# Shield_Amir_EDO_V_0_0.net
KiCad netlist of a schematic drawn in EasyEDA
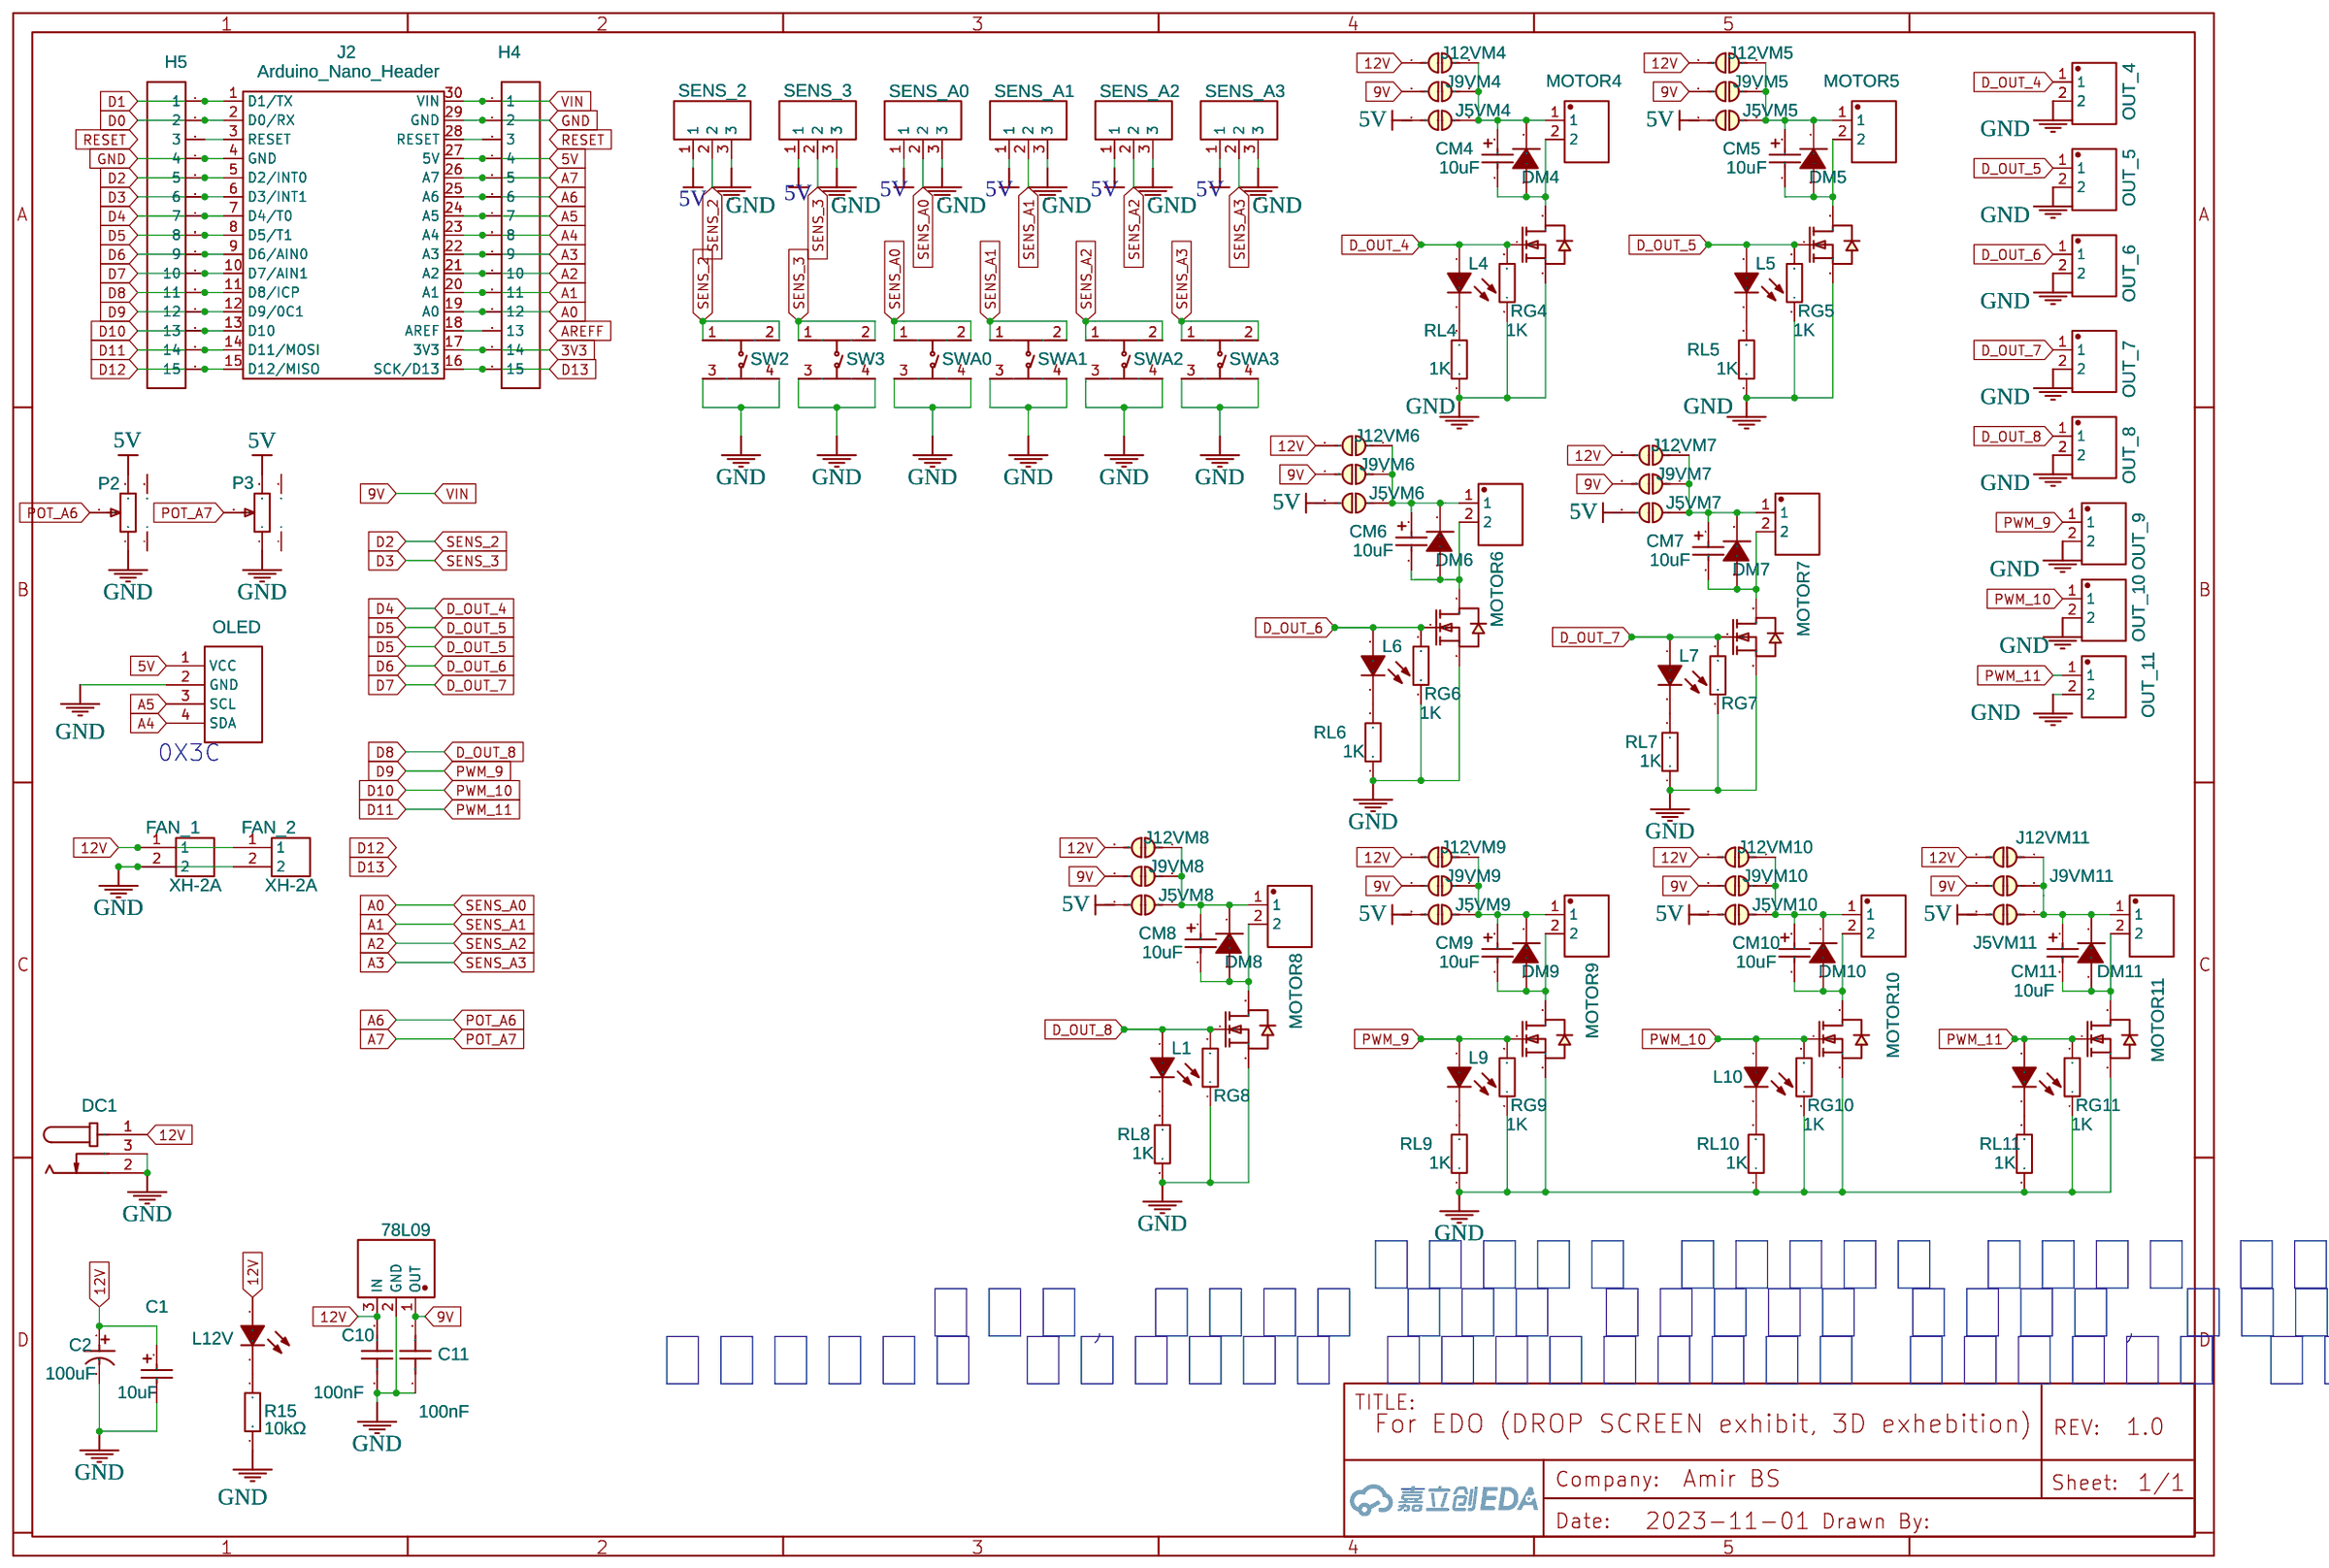
[diagram p0: schematic sheet]

(export (version "E")
  (design (tool "Eeschema 10.0.6"))
  (components
    (comp (ref "C1")
      (value "10uF")
      (fields (field (name "Manufacturer Part") "TAJA106K016RNJ") (field (name "Manufacturer") "Kyocera AVX"))
      (libsource (lib "") (part "TAJA106K016RNJ_1"))
    )
    (comp (ref "C2")
      (value "100uF")
      (fields
        (field (name "Manufacturer Part") "KM107M035E11RR0VH2FP0")
        (field (name "Manufacturer") "CX(承兴)")
      )
      (libsource (lib "") (part "100uF 35V 6.3*11"))
    )
    (comp (ref "C10")
      (value "100nF")
      (fields
        (field (name "Manufacturer Part") "CC0603KRX7R9BB104")
        (field (name "Manufacturer") "YAGEO(国巨)")
      )
      (libsource (lib "") (part "CC0603KRX7R9BB104"))
    )
    (comp (ref "C11")
      (value "100nF")
      (fields
        (field (name "Manufacturer Part") "CC0603KRX7R9BB104")
        (field (name "Manufacturer") "YAGEO(国巨)")
      )
      (libsource (lib "") (part "CC0603KRX7R9BB104"))
    )
    (comp (ref "CM4")
      (value "10uF")
      (fields (field (name "Manufacturer Part") "TAJA106K016RNJ") (field (name "Manufacturer") "Kyocera AVX"))
      (libsource (lib "") (part "TAJA106K016RNJ"))
    )
    (comp (ref "CM5")
      (value "10uF")
      (fields (field (name "Manufacturer Part") "TAJA106K016RNJ") (field (name "Manufacturer") "Kyocera AVX"))
      (libsource (lib "") (part "TAJA106K016RNJ"))
    )
    (comp (ref "CM6")
      (value "10uF")
      (fields (field (name "Manufacturer Part") "TAJA106K016RNJ") (field (name "Manufacturer") "Kyocera AVX"))
      (libsource (lib "") (part "TAJA106K016RNJ"))
    )
    (comp (ref "CM7")
      (value "10uF")
      (fields (field (name "Manufacturer Part") "TAJA106K016RNJ") (field (name "Manufacturer") "Kyocera AVX"))
      (libsource (lib "") (part "TAJA106K016RNJ"))
    )
    (comp (ref "CM8")
      (value "10uF")
      (fields (field (name "Manufacturer Part") "TAJA106K016RNJ") (field (name "Manufacturer") "Kyocera AVX"))
      (libsource (lib "") (part "TAJA106K016RNJ"))
    )
    (comp (ref "CM9")
      (value "10uF")
      (fields (field (name "Manufacturer Part") "TAJA106K016RNJ") (field (name "Manufacturer") "Kyocera AVX"))
      (libsource (lib "") (part "TAJA106K016RNJ"))
    )
    (comp (ref "CM10")
      (value "10uF")
      (fields (field (name "Manufacturer Part") "TAJA106K016RNJ") (field (name "Manufacturer") "Kyocera AVX"))
      (libsource (lib "") (part "TAJA106K016RNJ"))
    )
    (comp (ref "CM11")
      (value "10uF")
      (fields (field (name "Manufacturer Part") "TAJA106K016RNJ") (field (name "Manufacturer") "Kyocera AVX"))
      (libsource (lib "") (part "TAJA106K016RNJ"))
    )
    (comp (ref "DC1")
      (value "DC")
      (fields
        (field (name "BOM_Manufacturer Part") "DC005-2.0MM")
        (field (name "BOM_Supplier Part") "C111567")
      )
      (libsource (lib "") (part "DC005-2.0MM"))
    )
    (comp (ref "DM4")
      (value "1N4007")
      (fields (field (name "BOM_Manufacturer Part") "1N4007F") (field (name "BOM_Supplier Part") "C110856"))
      (libsource (lib "") (part "1N4007F"))
    )
    (comp (ref "DM5")
      (value "1N4007")
      (fields (field (name "BOM_Manufacturer Part") "1N4007F") (field (name "BOM_Supplier Part") "C110856"))
      (libsource (lib "") (part "1N4007F"))
    )
    (comp (ref "DM6")
      (value "1N4007")
      (fields (field (name "BOM_Manufacturer Part") "1N4007F") (field (name "BOM_Supplier Part") "C110856"))
      (libsource (lib "") (part "1N4007F"))
    )
    (comp (ref "DM7")
      (value "1N4007")
      (fields (field (name "BOM_Manufacturer Part") "1N4007F") (field (name "BOM_Supplier Part") "C110856"))
      (libsource (lib "") (part "1N4007F"))
    )
    (comp (ref "DM8")
      (value "1N4007")
      (fields (field (name "BOM_Manufacturer Part") "1N4007F") (field (name "BOM_Supplier Part") "C110856"))
      (libsource (lib "") (part "1N4007F"))
    )
    (comp (ref "DM9")
      (value "1N4007")
      (fields (field (name "BOM_Manufacturer Part") "1N4007F") (field (name "BOM_Supplier Part") "C110856"))
      (libsource (lib "") (part "1N4007F"))
    )
    (comp (ref "DM10")
      (value "1N4007")
      (fields (field (name "BOM_Manufacturer Part") "1N4007F") (field (name "BOM_Supplier Part") "C110856"))
      (libsource (lib "") (part "1N4007F"))
    )
    (comp (ref "DM11")
      (value "1N4007")
      (fields (field (name "BOM_Manufacturer Part") "1N4007F") (field (name "BOM_Supplier Part") "C110856"))
      (libsource (lib "") (part "1N4007F"))
    )
    (comp (ref "FAN_1")
      (value "XH-2A")
      (fields (field (name "Manufacturer") "BOOMELE(博穆精密)"))
      (libsource (lib "") (part "XH-2A"))
    )
    (comp (ref "FAN_2")
      (value "XH-2A")
      (fields (field (name "Manufacturer") "BOOMELE(博穆精密)"))
      (libsource (lib "") (part "XH-2A"))
    )
    (comp (ref "H4")
      (value "HDR-F-2.54_1x15")
      (fields (field (name "BOM_Supplier Part") "C124408"))
      (libsource (lib "") (part "HDR-F-2.54_1x15_1"))
    )
    (comp (ref "H5")
      (value "HDR-F-2.54_1x15")
      (fields (field (name "BOM_Supplier Part") "C124408"))
      (libsource (lib "") (part "HDR-F-2.54_1x15"))
    )
    (comp (ref "J2") (value "Arduino_Nano_Header") (libsource (lib "") (part "Arduino_Nano_Header")))
    (comp (ref "J5VM4") (value "JUMPER-SMT_2") (libsource (lib "") (part "JUMPER-SMT_2_1")))
    (comp (ref "J5VM5") (value "JUMPER-SMT_2") (libsource (lib "") (part "JUMPER-SMT_2_1")))
    (comp (ref "J5VM6") (value "JUMPER-SMT_2") (libsource (lib "") (part "JUMPER-SMT_2_1")))
    (comp (ref "J5VM7") (value "JUMPER-SMT_2") (libsource (lib "") (part "JUMPER-SMT_2_1")))
    (comp (ref "J5VM8") (value "JUMPER-SMT_2") (libsource (lib "") (part "JUMPER-SMT_2_1")))
    (comp (ref "J5VM9") (value "JUMPER-SMT_2") (libsource (lib "") (part "JUMPER-SMT_2_1")))
    (comp (ref "J5VM10") (value "JUMPER-SMT_2") (libsource (lib "") (part "JUMPER-SMT_2_1")))
    (comp (ref "J5VM11") (value "JUMPER-SMT_2") (libsource (lib "") (part "JUMPER-SMT_2_1")))
    (comp (ref "J9VM4") (value "JUMPER-SMT_2") (libsource (lib "") (part "JUMPER-SMT_2")))
    (comp (ref "J9VM5") (value "JUMPER-SMT_2") (libsource (lib "") (part "JUMPER-SMT_2")))
    (comp (ref "J9VM6") (value "JUMPER-SMT_2") (libsource (lib "") (part "JUMPER-SMT_2")))
    (comp (ref "J9VM7") (value "JUMPER-SMT_2") (libsource (lib "") (part "JUMPER-SMT_2")))
    (comp (ref "J9VM8") (value "JUMPER-SMT_2") (libsource (lib "") (part "JUMPER-SMT_2")))
    (comp (ref "J9VM9") (value "JUMPER-SMT_2") (libsource (lib "") (part "JUMPER-SMT_2")))
    (comp (ref "J9VM10") (value "JUMPER-SMT_2") (libsource (lib "") (part "JUMPER-SMT_2")))
    (comp (ref "J9VM11") (value "JUMPER-SMT_2") (libsource (lib "") (part "JUMPER-SMT_2")))
    (comp (ref "J12VM4") (value "JUMPER-SMT_2") (libsource (lib "") (part "JUMPER-SMT_2_2")))
    (comp (ref "J12VM5") (value "JUMPER-SMT_2") (libsource (lib "") (part "JUMPER-SMT_2_2")))
    (comp (ref "J12VM6") (value "JUMPER-SMT_2") (libsource (lib "") (part "JUMPER-SMT_2_2")))
    (comp (ref "J12VM7") (value "JUMPER-SMT_2") (libsource (lib "") (part "JUMPER-SMT_2_2")))
    (comp (ref "J12VM8") (value "JUMPER-SMT_2") (libsource (lib "") (part "JUMPER-SMT_2_2")))
    (comp (ref "J12VM9") (value "JUMPER-SMT_2") (libsource (lib "") (part "JUMPER-SMT_2_2")))
    (comp (ref "J12VM10") (value "JUMPER-SMT_2") (libsource (lib "") (part "JUMPER-SMT_2_2")))
    (comp (ref "J12VM11") (value "JUMPER-SMT_2") (libsource (lib "") (part "JUMPER-SMT_2_2")))
    (comp (ref "L1")
      (value "LED")
      (fields
        (field (name "BOM_Manufacturer Part") "19-217/BHC-ZL1M2RY/3T")
        (field (name "BOM_Supplier Part") "C72041")
      )
      (libsource (lib "") (part "19-217/BHC-ZL1M2RY/3T_1"))
    )
    (comp (ref "L4")
      (value "LED")
      (fields
        (field (name "BOM_Manufacturer Part") "19-217/BHC-ZL1M2RY/3T")
        (field (name "BOM_Supplier Part") "C72041")
      )
      (libsource (lib "") (part "19-217/BHC-ZL1M2RY/3T_1"))
    )
    (comp (ref "L5")
      (value "LED")
      (fields
        (field (name "BOM_Manufacturer Part") "19-217/BHC-ZL1M2RY/3T")
        (field (name "BOM_Supplier Part") "C72041")
      )
      (libsource (lib "") (part "19-217/BHC-ZL1M2RY/3T_1"))
    )
    (comp (ref "L6")
      (value "LED")
      (fields
        (field (name "BOM_Manufacturer Part") "19-217/BHC-ZL1M2RY/3T")
        (field (name "BOM_Supplier Part") "C72041")
      )
      (libsource (lib "") (part "19-217/BHC-ZL1M2RY/3T_1"))
    )
    (comp (ref "L7")
      (value "LED")
      (fields
        (field (name "BOM_Manufacturer Part") "19-217/BHC-ZL1M2RY/3T")
        (field (name "BOM_Supplier Part") "C72041")
      )
      (libsource (lib "") (part "19-217/BHC-ZL1M2RY/3T_1"))
    )
    (comp (ref "L9")
      (value "LED")
      (fields
        (field (name "BOM_Manufacturer Part") "19-217/BHC-ZL1M2RY/3T")
        (field (name "BOM_Supplier Part") "C72041")
      )
      (libsource (lib "") (part "19-217/BHC-ZL1M2RY/3T_1"))
    )
    (comp (ref "L10")
      (value "LED")
      (fields
        (field (name "BOM_Manufacturer Part") "19-217/BHC-ZL1M2RY/3T")
        (field (name "BOM_Supplier Part") "C72041")
      )
      (libsource (lib "") (part "19-217/BHC-ZL1M2RY/3T_1"))
    )
    (comp (ref "L11")
      (value "LED")
      (fields
        (field (name "BOM_Manufacturer Part") "19-217/BHC-ZL1M2RY/3T")
        (field (name "BOM_Supplier Part") "C72041")
      )
      (libsource (lib "") (part "19-217/BHC-ZL1M2RY/3T_1"))
    )
    (comp (ref "L12V")
      (value "LED")
      (fields
        (field (name "BOM_Manufacturer Part") "19-217/BHC-ZL1M2RY/3T")
        (field (name "BOM_Supplier Part") "C72041")
      )
      (libsource (lib "") (part "19-217/BHC-ZL1M2RY/3T"))
    )
    (comp (ref "MOTOR4")
      (value "KF2510-2A")
      (fields (field (name "BOM_Supplier Part") "C27543"))
      (libsource (lib "") (part "KF2510-2A"))
    )
    (comp (ref "MOTOR5")
      (value "KF2510-2A")
      (fields (field (name "BOM_Supplier Part") "C27543"))
      (libsource (lib "") (part "KF2510-2A"))
    )
    (comp (ref "MOTOR6")
      (value "KF2510-2A")
      (fields (field (name "BOM_Supplier Part") "C27543"))
      (libsource (lib "") (part "KF2510-2A"))
    )
    (comp (ref "MOTOR7")
      (value "KF2510-2A")
      (fields (field (name "BOM_Supplier Part") "C27543"))
      (libsource (lib "") (part "KF2510-2A"))
    )
    (comp (ref "MOTOR8")
      (value "KF2510-2A")
      (fields (field (name "BOM_Supplier Part") "C27543"))
      (libsource (lib "") (part "KF2510-2A"))
    )
    (comp (ref "MOTOR9")
      (value "KF2510-2A")
      (fields (field (name "BOM_Supplier Part") "C27543"))
      (libsource (lib "") (part "KF2510-2A"))
    )
    (comp (ref "MOTOR10")
      (value "KF2510-2A")
      (fields (field (name "BOM_Supplier Part") "C27543"))
      (libsource (lib "") (part "KF2510-2A"))
    )
    (comp (ref "MOTOR11")
      (value "KF2510-2A")
      (fields (field (name "BOM_Supplier Part") "C27543"))
      (libsource (lib "") (part "KF2510-2A"))
    )
    (comp (ref "OLED")
      (value "1.3 inch OLED SSH1106 I2C 128x64 copy")
      (libsource (lib "") (part "1.3 inch OLED SSH1106 I2C 128x64 copy"))
    )
    (comp (ref "OUT_4")
      (value "KF2510-2A")
      (fields (field (name "BOM_Supplier Part") "C27543"))
      (libsource (lib "") (part "KF2510-2A_1"))
    )
    (comp (ref "OUT_5")
      (value "KF2510-2A")
      (fields (field (name "BOM_Supplier Part") "C27543"))
      (libsource (lib "") (part "KF2510-2A_1"))
    )
    (comp (ref "OUT_6")
      (value "KF2510-2A")
      (fields (field (name "BOM_Supplier Part") "C27543"))
      (libsource (lib "") (part "KF2510-2A_1"))
    )
    (comp (ref "OUT_7")
      (value "KF2510-2A")
      (fields (field (name "BOM_Supplier Part") "C27543"))
      (libsource (lib "") (part "KF2510-2A_1"))
    )
    (comp (ref "OUT_8")
      (value "KF2510-2A")
      (fields (field (name "BOM_Supplier Part") "C27543"))
      (libsource (lib "") (part "KF2510-2A_1"))
    )
    (comp (ref "OUT_9")
      (value "KF2510-2A")
      (fields (field (name "BOM_Supplier Part") "C27543"))
      (libsource (lib "") (part "KF2510-2A_1"))
    )
    (comp (ref "OUT_10")
      (value "KF2510-2A")
      (fields (field (name "BOM_Supplier Part") "C27543"))
      (libsource (lib "") (part "KF2510-2A_1"))
    )
    (comp (ref "OUT_11")
      (value "KF2510-2A")
      (fields (field (name "BOM_Supplier Part") "C27543"))
      (libsource (lib "") (part "KF2510-2A_1"))
    )
    (comp (ref "P2")
      (value "长柄旋转电位器")
      (fields (field (name "BOM_Supplier Part") "C2874842"))
      (libsource (lib "") (part "长柄旋转电位器"))
    )
    (comp (ref "P3")
      (value "长柄旋转电位器")
      (fields (field (name "BOM_Supplier Part") "C2874842"))
      (libsource (lib "") (part "长柄旋转电位器"))
    )
    (comp (ref "Q2")
      (value "Q")
      (fields (field (name "BOM_Manufacturer Part") "JSM2302") (field (name "BOM_Supplier Part") "C916403"))
      (libsource (lib "") (part "JSM2302_1"))
    )
    (comp (ref "QM4")
      (value "Q")
      (fields (field (name "BOM_Manufacturer Part") "JSM2302") (field (name "BOM_Supplier Part") "C916403"))
      (libsource (lib "") (part "JSM2302"))
    )
    (comp (ref "QM5")
      (value "Q")
      (fields (field (name "BOM_Manufacturer Part") "JSM2302") (field (name "BOM_Supplier Part") "C916403"))
      (libsource (lib "") (part "JSM2302"))
    )
    (comp (ref "QM6")
      (value "Q")
      (fields (field (name "BOM_Manufacturer Part") "JSM2302") (field (name "BOM_Supplier Part") "C916403"))
      (libsource (lib "") (part "JSM2302"))
    )
    (comp (ref "QM7")
      (value "Q")
      (fields (field (name "BOM_Manufacturer Part") "JSM2302") (field (name "BOM_Supplier Part") "C916403"))
      (libsource (lib "") (part "JSM2302"))
    )
    (comp (ref "QM8")
      (value "Q")
      (fields (field (name "BOM_Manufacturer Part") "JSM2302") (field (name "BOM_Supplier Part") "C916403"))
      (libsource (lib "") (part "JSM2302"))
    )
    (comp (ref "QM9")
      (value "Q")
      (fields (field (name "BOM_Manufacturer Part") "JSM2302") (field (name "BOM_Supplier Part") "C916403"))
      (libsource (lib "") (part "JSM2302"))
    )
    (comp (ref "QM10")
      (value "Q")
      (fields (field (name "BOM_Manufacturer Part") "JSM2302") (field (name "BOM_Supplier Part") "C916403"))
      (libsource (lib "") (part "JSM2302"))
    )
    (comp (ref "R15")
      (value "10kΩ")
      (fields
        (field (name "BOM_Manufacturer Part") "0603WAF1002T5E")
        (field (name "BOM_Supplier Part") "C25804")
      )
      (libsource (lib "") (part "0603WAF1002T5E"))
    )
    (comp (ref "RG4")
      (value "1K")
      (fields
        (field (name "BOM_Manufacturer Part") "0603WAF1001T5E")
        (field (name "BOM_Supplier Part") "C21190")
      )
      (libsource (lib "") (part "0603WAF1001T5E_1"))
    )
    (comp (ref "RG5")
      (value "1K")
      (fields
        (field (name "BOM_Manufacturer Part") "0603WAF1001T5E")
        (field (name "BOM_Supplier Part") "C21190")
      )
      (libsource (lib "") (part "0603WAF1001T5E_1"))
    )
    (comp (ref "RG6")
      (value "1K")
      (fields
        (field (name "BOM_Manufacturer Part") "0603WAF1001T5E")
        (field (name "BOM_Supplier Part") "C21190")
      )
      (libsource (lib "") (part "0603WAF1001T5E_1"))
    )
    (comp (ref "RG7")
      (value "1K")
      (fields
        (field (name "BOM_Manufacturer Part") "0603WAF1001T5E")
        (field (name "BOM_Supplier Part") "C21190")
      )
      (libsource (lib "") (part "0603WAF1001T5E_1"))
    )
    (comp (ref "RG8")
      (value "1K")
      (fields
        (field (name "BOM_Manufacturer Part") "0603WAF1001T5E")
        (field (name "BOM_Supplier Part") "C21190")
      )
      (libsource (lib "") (part "0603WAF1001T5E_1"))
    )
    (comp (ref "RG9")
      (value "1K")
      (fields
        (field (name "BOM_Manufacturer Part") "0603WAF1001T5E")
        (field (name "BOM_Supplier Part") "C21190")
      )
      (libsource (lib "") (part "0603WAF1001T5E_1"))
    )
    (comp (ref "RG10")
      (value "1K")
      (fields
        (field (name "BOM_Manufacturer Part") "0603WAF1001T5E")
        (field (name "BOM_Supplier Part") "C21190")
      )
      (libsource (lib "") (part "0603WAF1001T5E_1"))
    )
    (comp (ref "RG11")
      (value "1K")
      (fields
        (field (name "BOM_Manufacturer Part") "0603WAF1001T5E")
        (field (name "BOM_Supplier Part") "C21190")
      )
      (libsource (lib "") (part "0603WAF1001T5E_1"))
    )
    (comp (ref "RL4")
      (value "1K")
      (fields
        (field (name "BOM_Manufacturer Part") "0603WAF1001T5E")
        (field (name "BOM_Supplier Part") "C21190")
      )
      (libsource (lib "") (part "0603WAF1001T5E"))
    )
    (comp (ref "RL5")
      (value "1K")
      (fields
        (field (name "BOM_Manufacturer Part") "0603WAF1001T5E")
        (field (name "BOM_Supplier Part") "C21190")
      )
      (libsource (lib "") (part "0603WAF1001T5E"))
    )
    (comp (ref "RL6")
      (value "1K")
      (fields
        (field (name "BOM_Manufacturer Part") "0603WAF1001T5E")
        (field (name "BOM_Supplier Part") "C21190")
      )
      (libsource (lib "") (part "0603WAF1001T5E"))
    )
    (comp (ref "RL7")
      (value "1K")
      (fields
        (field (name "BOM_Manufacturer Part") "0603WAF1001T5E")
        (field (name "BOM_Supplier Part") "C21190")
      )
      (libsource (lib "") (part "0603WAF1001T5E"))
    )
    (comp (ref "RL8")
      (value "1K")
      (fields
        (field (name "BOM_Manufacturer Part") "0603WAF1001T5E")
        (field (name "BOM_Supplier Part") "C21190")
      )
      (libsource (lib "") (part "0603WAF1001T5E"))
    )
    (comp (ref "RL9")
      (value "1K")
      (fields
        (field (name "BOM_Manufacturer Part") "0603WAF1001T5E")
        (field (name "BOM_Supplier Part") "C21190")
      )
      (libsource (lib "") (part "0603WAF1001T5E"))
    )
    (comp (ref "RL10")
      (value "1K")
      (fields
        (field (name "BOM_Manufacturer Part") "0603WAF1001T5E")
        (field (name "BOM_Supplier Part") "C21190")
      )
      (libsource (lib "") (part "0603WAF1001T5E"))
    )
    (comp (ref "RL11")
      (value "1K")
      (fields
        (field (name "BOM_Manufacturer Part") "0603WAF1001T5E")
        (field (name "BOM_Supplier Part") "C21190")
      )
      (libsource (lib "") (part "0603WAF1001T5E"))
    )
    (comp (ref "SENS_2")
      (value "FK2510")
      (fields (field (name "Manufacturer Part") "2510-3A") (field (name "Manufacturer") "BOOMELE(博穆精密)"))
      (libsource (lib "") (part "kf2510_3A_1"))
    )
    (comp (ref "SENS_3")
      (value "FK2510")
      (fields (field (name "Manufacturer Part") "2510-3A") (field (name "Manufacturer") "BOOMELE(博穆精密)"))
      (libsource (lib "") (part "kf2510_3A_1"))
    )
    (comp (ref "SENS_A0")
      (value "FK2510")
      (fields (field (name "Manufacturer Part") "2510-3A") (field (name "Manufacturer") "BOOMELE(博穆精密)"))
      (libsource (lib "") (part "kf2510_3A"))
    )
    (comp (ref "SENS_A1")
      (value "FK2510")
      (fields (field (name "Manufacturer Part") "2510-3A") (field (name "Manufacturer") "BOOMELE(博穆精密)"))
      (libsource (lib "") (part "kf2510_3A"))
    )
    (comp (ref "SENS_A2")
      (value "FK2510")
      (fields (field (name "Manufacturer Part") "2510-3A") (field (name "Manufacturer") "BOOMELE(博穆精密)"))
      (libsource (lib "") (part "kf2510_3A"))
    )
    (comp (ref "SENS_A3")
      (value "FK2510")
      (fields (field (name "Manufacturer Part") "2510-3A") (field (name "Manufacturer") "BOOMELE(博穆精密)"))
      (libsource (lib "") (part "kf2510_3A"))
    )
    (comp (ref "SW2")
      (value "TC-6610-7-160G")
      (fields (field (name "Manufacturer") "HCTL(华灿天禄)"))
      (libsource (lib "") (part "TC-6610-7-160G_1"))
    )
    (comp (ref "SW3")
      (value "TC-6610-7-160G")
      (fields (field (name "Manufacturer") "HCTL(华灿天禄)"))
      (libsource (lib "") (part "TC-6610-7-160G_1"))
    )
    (comp (ref "SWA0")
      (value "TC-6610-7-160G")
      (fields (field (name "Manufacturer") "HCTL(华灿天禄)"))
      (libsource (lib "") (part "TC-6610-7-160G"))
    )
    (comp (ref "SWA1")
      (value "TC-6610-7-160G")
      (fields (field (name "Manufacturer") "HCTL(华灿天禄)"))
      (libsource (lib "") (part "TC-6610-7-160G"))
    )
    (comp (ref "SWA2")
      (value "TC-6610-7-160G")
      (fields (field (name "Manufacturer") "HCTL(华灿天禄)"))
      (libsource (lib "") (part "TC-6610-7-160G"))
    )
    (comp (ref "SWA3")
      (value "TC-6610-7-160G")
      (fields (field (name "Manufacturer") "HCTL(华灿天禄)"))
      (libsource (lib "") (part "TC-6610-7-160G"))
    )
    (comp (ref "U5")
      (value "78L09")
      (fields (field (name "Manufacturer Part") "78L09U 78L09") (field (name "Manufacturer") "CBI(创基)"))
      (libsource (lib "") (part "78L09U 78L09"))
    )
  )
  (nets
    (net (code "1") (name "3V3") (class "Default")
      (node (ref "H4") (pin "14") (pinfunction "14_14") (pintype "unspecified"))
      (node (ref "J2") (pin "17") (pinfunction "3V3_17") (pintype "unspecified"))
    )
    (net (code "2") (name "5V") (class "Default")
      (node (ref "H4") (pin "4") (pinfunction "4_4") (pintype "unspecified"))
      (node (ref "J2") (pin "27") (pinfunction "5V_27") (pintype "unspecified"))
      (node (ref "J5VM10") (pin "2") (pinfunction "2_2") (pintype "bidirectional"))
      (node (ref "J5VM11") (pin "2") (pinfunction "2_2") (pintype "bidirectional"))
      (node (ref "J5VM4") (pin "2") (pinfunction "2_2") (pintype "bidirectional"))
      (node (ref "J5VM5") (pin "2") (pinfunction "2_2") (pintype "bidirectional"))
      (node (ref "J5VM6") (pin "2") (pinfunction "2_2") (pintype "bidirectional"))
      (node (ref "J5VM7") (pin "2") (pinfunction "2_2") (pintype "bidirectional"))
      (node (ref "J5VM8") (pin "2") (pinfunction "2_2") (pintype "bidirectional"))
      (node (ref "J5VM9") (pin "2") (pinfunction "2_2") (pintype "bidirectional"))
      (node (ref "OLED") (pin "1") (pinfunction "VCC_1") (pintype "passive"))
      (node (ref "P2") (pin "3") (pinfunction "3_3") (pintype "input"))
      (node (ref "P3") (pin "3") (pinfunction "3_3") (pintype "input"))
      (node (ref "SENS_2") (pin "1") (pinfunction "1_1") (pintype "unspecified"))
      (node (ref "SENS_3") (pin "1") (pinfunction "1_1") (pintype "unspecified"))
      (node (ref "SENS_A0") (pin "1") (pinfunction "1_1") (pintype "unspecified"))
      (node (ref "SENS_A1") (pin "1") (pinfunction "1_1") (pintype "unspecified"))
      (node (ref "SENS_A2") (pin "1") (pinfunction "1_1") (pintype "unspecified"))
      (node (ref "SENS_A3") (pin "1") (pinfunction "1_1") (pintype "unspecified"))
    )
    (net (code "3") (name "9V") (class "Default")
      (node (ref "C11") (pin "2") (pinfunction "2_2") (pintype "unspecified"))
      (node (ref "H4") (pin "1") (pinfunction "1_1") (pintype "unspecified"))
      (node (ref "J2") (pin "30") (pinfunction "VIN_30") (pintype "unspecified"))
      (node (ref "J9VM10") (pin "2") (pinfunction "2_2") (pintype "bidirectional"))
      (node (ref "J9VM11") (pin "2") (pinfunction "2_2") (pintype "bidirectional"))
      (node (ref "J9VM4") (pin "2") (pinfunction "2_2") (pintype "bidirectional"))
      (node (ref "J9VM5") (pin "2") (pinfunction "2_2") (pintype "bidirectional"))
      (node (ref "J9VM6") (pin "2") (pinfunction "2_2") (pintype "bidirectional"))
      (node (ref "J9VM7") (pin "2") (pinfunction "2_2") (pintype "bidirectional"))
      (node (ref "J9VM8") (pin "2") (pinfunction "2_2") (pintype "bidirectional"))
      (node (ref "J9VM9") (pin "2") (pinfunction "2_2") (pintype "bidirectional"))
      (node (ref "U5") (pin "1") (pinfunction "OUT_1") (pintype "unspecified"))
    )
    (net (code "4") (name "12V") (class "Default")
      (node (ref "C1") (pin "1") (pinfunction "1_1") (pintype "input"))
      (node (ref "C10") (pin "2") (pinfunction "2_2") (pintype "unspecified"))
      (node (ref "C2") (pin "1") (pinfunction "1_1") (pintype "input"))
      (node (ref "DC1") (pin "1") (pinfunction "1_1") (pintype "unspecified"))
      (node (ref "FAN_1") (pin "1") (pinfunction "1_1") (pintype "unspecified"))
      (node (ref "FAN_2") (pin "1") (pinfunction "1_1") (pintype "unspecified"))
      (node (ref "J12VM10") (pin "2") (pinfunction "2_2") (pintype "bidirectional"))
      (node (ref "J12VM11") (pin "2") (pinfunction "2_2") (pintype "bidirectional"))
      (node (ref "J12VM4") (pin "2") (pinfunction "2_2") (pintype "bidirectional"))
      (node (ref "J12VM5") (pin "2") (pinfunction "2_2") (pintype "bidirectional"))
      (node (ref "J12VM6") (pin "2") (pinfunction "2_2") (pintype "bidirectional"))
      (node (ref "J12VM7") (pin "2") (pinfunction "2_2") (pintype "bidirectional"))
      (node (ref "J12VM8") (pin "2") (pinfunction "2_2") (pintype "bidirectional"))
      (node (ref "J12VM9") (pin "2") (pinfunction "2_2") (pintype "bidirectional"))
      (node (ref "L12V") (pin "1") (pinfunction "A_1") (pintype "input"))
      (node (ref "U5") (pin "3") (pinfunction "IN_3") (pintype "unspecified"))
    )
    (net (code "5") (name "A0") (class "Default")
      (node (ref "H4") (pin "12") (pinfunction "12_12") (pintype "unspecified"))
      (node (ref "J2") (pin "19") (pinfunction "A0_19") (pintype "unspecified"))
      (node (ref "SENS_A0") (pin "2") (pinfunction "2_2") (pintype "unspecified"))
      (node (ref "SWA0") (pin "1") (pinfunction "1_1") (pintype "unspecified"))
      (node (ref "SWA0") (pin "2") (pinfunction "2_2") (pintype "unspecified"))
    )
    (net (code "6") (name "A1") (class "Default")
      (node (ref "H4") (pin "11") (pinfunction "11_11") (pintype "unspecified"))
      (node (ref "J2") (pin "20") (pinfunction "A1_20") (pintype "unspecified"))
      (node (ref "SENS_A1") (pin "2") (pinfunction "2_2") (pintype "unspecified"))
      (node (ref "SWA1") (pin "1") (pinfunction "1_1") (pintype "unspecified"))
      (node (ref "SWA1") (pin "2") (pinfunction "2_2") (pintype "unspecified"))
    )
    (net (code "7") (name "A2") (class "Default")
      (node (ref "H4") (pin "10") (pinfunction "10_10") (pintype "unspecified"))
      (node (ref "J2") (pin "21") (pinfunction "A2_21") (pintype "unspecified"))
      (node (ref "SENS_A2") (pin "2") (pinfunction "2_2") (pintype "unspecified"))
      (node (ref "SWA2") (pin "1") (pinfunction "1_1") (pintype "unspecified"))
      (node (ref "SWA2") (pin "2") (pinfunction "2_2") (pintype "unspecified"))
    )
    (net (code "8") (name "A3") (class "Default")
      (node (ref "H4") (pin "9") (pinfunction "9_9") (pintype "unspecified"))
      (node (ref "J2") (pin "22") (pinfunction "A3_22") (pintype "unspecified"))
      (node (ref "SENS_A3") (pin "2") (pinfunction "2_2") (pintype "unspecified"))
      (node (ref "SWA3") (pin "1") (pinfunction "1_1") (pintype "unspecified"))
      (node (ref "SWA3") (pin "2") (pinfunction "2_2") (pintype "unspecified"))
    )
    (net (code "9") (name "A4") (class "Default")
      (node (ref "H4") (pin "8") (pinfunction "8_8") (pintype "unspecified"))
      (node (ref "J2") (pin "23") (pinfunction "A4_23") (pintype "unspecified"))
      (node (ref "OLED") (pin "4") (pinfunction "SDA_4") (pintype "bidirectional"))
    )
    (net (code "10") (name "A5") (class "Default")
      (node (ref "H4") (pin "7") (pinfunction "7_7") (pintype "unspecified"))
      (node (ref "J2") (pin "24") (pinfunction "A5_24") (pintype "unspecified"))
      (node (ref "OLED") (pin "3") (pinfunction "SCL_3") (pintype "bidirectional"))
    )
    (net (code "11") (name "A6") (class "Default")
      (node (ref "H4") (pin "6") (pinfunction "6_6") (pintype "unspecified"))
      (node (ref "J2") (pin "25") (pinfunction "A6_25") (pintype "unspecified"))
      (node (ref "P2") (pin "2") (pinfunction "2_2") (pintype "input"))
    )
    (net (code "12") (name "A7") (class "Default")
      (node (ref "H4") (pin "5") (pinfunction "5_5") (pintype "unspecified"))
      (node (ref "J2") (pin "26") (pinfunction "A7_26") (pintype "unspecified"))
      (node (ref "P3") (pin "2") (pinfunction "2_2") (pintype "input"))
    )
    (net (code "14") (name "D0") (class "Default")
      (node (ref "H5") (pin "2") (pinfunction "2_2") (pintype "unspecified"))
      (node (ref "J2") (pin "2") (pinfunction "D0/RX_2") (pintype "unspecified"))
    )
    (net (code "15") (name "D1") (class "Default")
      (node (ref "H5") (pin "1") (pinfunction "1_1") (pintype "unspecified"))
      (node (ref "J2") (pin "1") (pinfunction "D1/TX_1") (pintype "unspecified"))
    )
    (net (code "16") (name "D2") (class "Default")
      (node (ref "H5") (pin "5") (pinfunction "5_5") (pintype "unspecified"))
      (node (ref "J2") (pin "5") (pinfunction "D2/INT0_5") (pintype "unspecified"))
      (node (ref "SENS_2") (pin "2") (pinfunction "2_2") (pintype "unspecified"))
      (node (ref "SW2") (pin "1") (pinfunction "1_1") (pintype "unspecified"))
      (node (ref "SW2") (pin "2") (pinfunction "2_2") (pintype "unspecified"))
    )
    (net (code "17") (name "D3") (class "Default")
      (node (ref "H5") (pin "6") (pinfunction "6_6") (pintype "unspecified"))
      (node (ref "J2") (pin "6") (pinfunction "D3/INT1_6") (pintype "unspecified"))
      (node (ref "SENS_3") (pin "2") (pinfunction "2_2") (pintype "unspecified"))
      (node (ref "SW3") (pin "1") (pinfunction "1_1") (pintype "unspecified"))
      (node (ref "SW3") (pin "2") (pinfunction "2_2") (pintype "unspecified"))
    )
    (net (code "18") (name "D4") (class "Default")
      (node (ref "H5") (pin "7") (pinfunction "7_7") (pintype "unspecified"))
      (node (ref "J2") (pin "7") (pinfunction "D4/T0_7") (pintype "unspecified"))
      (node (ref "L4") (pin "1") (pinfunction "A_1") (pintype "input"))
      (node (ref "OUT_4") (pin "1") (pinfunction "1_1") (pintype "unspecified"))
      (node (ref "QM4") (pin "1") (pinfunction "G_1") (pintype "unspecified"))
      (node (ref "RG4") (pin "2") (pinfunction "2_2") (pintype "input"))
    )
    (net (code "19") (name "D5") (class "Default")
      (node (ref "H5") (pin "8") (pinfunction "8_8") (pintype "unspecified"))
      (node (ref "J2") (pin "8") (pinfunction "D5/T1_8") (pintype "unspecified"))
      (node (ref "L5") (pin "1") (pinfunction "A_1") (pintype "input"))
      (node (ref "OUT_5") (pin "1") (pinfunction "1_1") (pintype "unspecified"))
      (node (ref "QM5") (pin "1") (pinfunction "G_1") (pintype "unspecified"))
      (node (ref "RG5") (pin "2") (pinfunction "2_2") (pintype "input"))
    )
    (net (code "20") (name "D6") (class "Default")
      (node (ref "H5") (pin "9") (pinfunction "9_9") (pintype "unspecified"))
      (node (ref "J2") (pin "9") (pinfunction "D6/AIN0_9") (pintype "unspecified"))
      (node (ref "L6") (pin "1") (pinfunction "A_1") (pintype "input"))
      (node (ref "OUT_6") (pin "1") (pinfunction "1_1") (pintype "unspecified"))
      (node (ref "QM6") (pin "1") (pinfunction "G_1") (pintype "unspecified"))
      (node (ref "RG6") (pin "2") (pinfunction "2_2") (pintype "input"))
    )
    (net (code "21") (name "D7") (class "Default")
      (node (ref "H5") (pin "10") (pinfunction "10_10") (pintype "unspecified"))
      (node (ref "J2") (pin "10") (pinfunction "D7/AIN1_10") (pintype "unspecified"))
      (node (ref "L7") (pin "1") (pinfunction "A_1") (pintype "input"))
      (node (ref "OUT_7") (pin "1") (pinfunction "1_1") (pintype "unspecified"))
      (node (ref "QM7") (pin "1") (pinfunction "G_1") (pintype "unspecified"))
      (node (ref "RG7") (pin "2") (pinfunction "2_2") (pintype "input"))
    )
    (net (code "22") (name "D8") (class "Default")
      (node (ref "H5") (pin "11") (pinfunction "11_11") (pintype "unspecified"))
      (node (ref "J2") (pin "11") (pinfunction "D8/ICP_11") (pintype "unspecified"))
      (node (ref "L1") (pin "1") (pinfunction "A_1") (pintype "input"))
      (node (ref "OUT_8") (pin "1") (pinfunction "1_1") (pintype "unspecified"))
      (node (ref "QM8") (pin "1") (pinfunction "G_1") (pintype "unspecified"))
      (node (ref "RG8") (pin "2") (pinfunction "2_2") (pintype "input"))
    )
    (net (code "23") (name "D9") (class "Default")
      (node (ref "H5") (pin "12") (pinfunction "12_12") (pintype "unspecified"))
      (node (ref "J2") (pin "12") (pinfunction "D9/0C1_12") (pintype "unspecified"))
      (node (ref "L9") (pin "1") (pinfunction "A_1") (pintype "input"))
      (node (ref "OUT_9") (pin "1") (pinfunction "1_1") (pintype "unspecified"))
      (node (ref "QM9") (pin "1") (pinfunction "G_1") (pintype "unspecified"))
      (node (ref "RG9") (pin "2") (pinfunction "2_2") (pintype "input"))
    )
    (net (code "24") (name "D10") (class "Default")
      (node (ref "H5") (pin "13") (pinfunction "13_13") (pintype "unspecified"))
      (node (ref "J2") (pin "13") (pinfunction "D10_13") (pintype "unspecified"))
      (node (ref "L10") (pin "1") (pinfunction "A_1") (pintype "input"))
      (node (ref "OUT_10") (pin "1") (pinfunction "1_1") (pintype "unspecified"))
      (node (ref "QM10") (pin "1") (pinfunction "G_1") (pintype "unspecified"))
      (node (ref "RG10") (pin "2") (pinfunction "2_2") (pintype "input"))
    )
    (net (code "25") (name "D11") (class "Default")
      (node (ref "H5") (pin "14") (pinfunction "14_14") (pintype "unspecified"))
      (node (ref "J2") (pin "14") (pinfunction "D11/MOSI_14") (pintype "unspecified"))
      (node (ref "L11") (pin "1") (pinfunction "A_1") (pintype "input"))
      (node (ref "OUT_11") (pin "1") (pinfunction "1_1") (pintype "unspecified"))
      (node (ref "Q2") (pin "1") (pinfunction "G_1") (pintype "unspecified"))
      (node (ref "RG11") (pin "2") (pinfunction "2_2") (pintype "input"))
    )
    (net (code "26") (name "D12") (class "Default")
      (node (ref "H5") (pin "15") (pinfunction "15_15") (pintype "unspecified"))
      (node (ref "J2") (pin "15") (pinfunction "D12/MISO_15") (pintype "unspecified"))
    )
    (net (code "27") (name "D13") (class "Default")
      (node (ref "H4") (pin "15") (pinfunction "15_15") (pintype "unspecified"))
      (node (ref "J2") (pin "16") (pinfunction "SCK/D13_16") (pintype "unspecified"))
    )
    (net (code "28") (name "GND") (class "Default")
      (node (ref "C1") (pin "2") (pinfunction "2_2") (pintype "input"))
      (node (ref "C10") (pin "1") (pinfunction "1_1") (pintype "unspecified"))
      (node (ref "C11") (pin "1") (pinfunction "1_1") (pintype "unspecified"))
      (node (ref "C2") (pin "2") (pinfunction "2_2") (pintype "input"))
      (node (ref "DC1") (pin "2") (pinfunction "2_2") (pintype "unspecified"))
      (node (ref "DC1") (pin "3") (pinfunction "3_3") (pintype "unspecified"))
      (node (ref "FAN_1") (pin "2") (pinfunction "2_2") (pintype "unspecified"))
      (node (ref "FAN_2") (pin "2") (pinfunction "2_2") (pintype "unspecified"))
      (node (ref "H4") (pin "2") (pinfunction "2_2") (pintype "unspecified"))
      (node (ref "H5") (pin "4") (pinfunction "4_4") (pintype "unspecified"))
      (node (ref "J2") (pin "29") (pinfunction "GND_29") (pintype "unspecified"))
      (node (ref "J2") (pin "4") (pinfunction "GND_4") (pintype "unspecified"))
      (node (ref "OLED") (pin "2") (pinfunction "GND_2") (pintype "passive"))
      (node (ref "OUT_10") (pin "2") (pinfunction "2_2") (pintype "unspecified"))
      (node (ref "OUT_11") (pin "2") (pinfunction "2_2") (pintype "unspecified"))
      (node (ref "OUT_4") (pin "2") (pinfunction "2_2") (pintype "unspecified"))
      (node (ref "OUT_5") (pin "2") (pinfunction "2_2") (pintype "unspecified"))
      (node (ref "OUT_6") (pin "2") (pinfunction "2_2") (pintype "unspecified"))
      (node (ref "OUT_7") (pin "2") (pinfunction "2_2") (pintype "unspecified"))
      (node (ref "OUT_8") (pin "2") (pinfunction "2_2") (pintype "unspecified"))
      (node (ref "OUT_9") (pin "2") (pinfunction "2_2") (pintype "unspecified"))
      (node (ref "P2") (pin "1") (pinfunction "1_1") (pintype "input"))
      (node (ref "P3") (pin "1") (pinfunction "1_1") (pintype "input"))
      (node (ref "Q2") (pin "2") (pinfunction "S_2") (pintype "unspecified"))
      (node (ref "QM10") (pin "2") (pinfunction "S_2") (pintype "unspecified"))
      (node (ref "QM4") (pin "2") (pinfunction "S_2") (pintype "unspecified"))
      (node (ref "QM5") (pin "2") (pinfunction "S_2") (pintype "unspecified"))
      (node (ref "QM6") (pin "2") (pinfunction "S_2") (pintype "unspecified"))
      (node (ref "QM7") (pin "2") (pinfunction "S_2") (pintype "unspecified"))
      (node (ref "QM8") (pin "2") (pinfunction "S_2") (pintype "unspecified"))
      (node (ref "QM9") (pin "2") (pinfunction "S_2") (pintype "unspecified"))
      (node (ref "R15") (pin "2") (pinfunction "2_2") (pintype "input"))
      (node (ref "RG10") (pin "1") (pinfunction "1_1") (pintype "input"))
      (node (ref "RG11") (pin "1") (pinfunction "1_1") (pintype "input"))
      (node (ref "RG4") (pin "1") (pinfunction "1_1") (pintype "input"))
      (node (ref "RG5") (pin "1") (pinfunction "1_1") (pintype "input"))
      (node (ref "RG6") (pin "1") (pinfunction "1_1") (pintype "input"))
      (node (ref "RG7") (pin "1") (pinfunction "1_1") (pintype "input"))
      (node (ref "RG8") (pin "1") (pinfunction "1_1") (pintype "input"))
      (node (ref "RG9") (pin "1") (pinfunction "1_1") (pintype "input"))
      (node (ref "RL10") (pin "1") (pinfunction "1_1") (pintype "input"))
      (node (ref "RL11") (pin "1") (pinfunction "1_1") (pintype "input"))
      (node (ref "RL4") (pin "1") (pinfunction "1_1") (pintype "input"))
      (node (ref "RL5") (pin "1") (pinfunction "1_1") (pintype "input"))
      (node (ref "RL6") (pin "1") (pinfunction "1_1") (pintype "input"))
      (node (ref "RL7") (pin "1") (pinfunction "1_1") (pintype "input"))
      (node (ref "RL8") (pin "1") (pinfunction "1_1") (pintype "input"))
      (node (ref "RL9") (pin "1") (pinfunction "1_1") (pintype "input"))
      (node (ref "SENS_2") (pin "3") (pinfunction "3_3") (pintype "unspecified"))
      (node (ref "SENS_3") (pin "3") (pinfunction "3_3") (pintype "unspecified"))
      (node (ref "SENS_A0") (pin "3") (pinfunction "3_3") (pintype "unspecified"))
      (node (ref "SENS_A1") (pin "3") (pinfunction "3_3") (pintype "unspecified"))
      (node (ref "SENS_A2") (pin "3") (pinfunction "3_3") (pintype "unspecified"))
      (node (ref "SENS_A3") (pin "3") (pinfunction "3_3") (pintype "unspecified"))
      (node (ref "SW2") (pin "3") (pinfunction "3_3") (pintype "unspecified"))
      (node (ref "SW2") (pin "4") (pinfunction "4_4") (pintype "unspecified"))
      (node (ref "SW3") (pin "3") (pinfunction "3_3") (pintype "unspecified"))
      (node (ref "SW3") (pin "4") (pinfunction "4_4") (pintype "unspecified"))
      (node (ref "SWA0") (pin "3") (pinfunction "3_3") (pintype "unspecified"))
      (node (ref "SWA0") (pin "4") (pinfunction "4_4") (pintype "unspecified"))
      (node (ref "SWA1") (pin "3") (pinfunction "3_3") (pintype "unspecified"))
      (node (ref "SWA1") (pin "4") (pinfunction "4_4") (pintype "unspecified"))
      (node (ref "SWA2") (pin "3") (pinfunction "3_3") (pintype "unspecified"))
      (node (ref "SWA2") (pin "4") (pinfunction "4_4") (pintype "unspecified"))
      (node (ref "SWA3") (pin "3") (pinfunction "3_3") (pintype "unspecified"))
      (node (ref "SWA3") (pin "4") (pinfunction "4_4") (pintype "unspecified"))
      (node (ref "U5") (pin "2") (pinfunction "GND_2") (pintype "unspecified"))
    )
    (net (code "29") (name "Net-(DM4-A)") (class "Default")
      (node (ref "CM4") (pin "2") (pinfunction "2_2") (pintype "input"))
      (node (ref "DM4") (pin "2") (pinfunction "A_2") (pintype "unspecified"))
      (node (ref "MOTOR4") (pin "2") (pinfunction "2_2") (pintype "unspecified"))
      (node (ref "QM4") (pin "3") (pinfunction "D_3") (pintype "unspecified"))
    )
    (net (code "30") (name "Net-(DM4-C)") (class "Default")
      (node (ref "CM4") (pin "1") (pinfunction "1_1") (pintype "input"))
      (node (ref "DM4") (pin "1") (pinfunction "C_1") (pintype "unspecified"))
      (node (ref "J12VM4") (pin "1") (pinfunction "1_1") (pintype "bidirectional"))
      (node (ref "J5VM4") (pin "1") (pinfunction "1_1") (pintype "bidirectional"))
      (node (ref "J9VM4") (pin "1") (pinfunction "1_1") (pintype "bidirectional"))
      (node (ref "MOTOR4") (pin "1") (pinfunction "1_1") (pintype "unspecified"))
    )
    (net (code "31") (name "Net-(DM5-A)") (class "Default")
      (node (ref "CM5") (pin "2") (pinfunction "2_2") (pintype "input"))
      (node (ref "DM5") (pin "2") (pinfunction "A_2") (pintype "unspecified"))
      (node (ref "MOTOR5") (pin "2") (pinfunction "2_2") (pintype "unspecified"))
      (node (ref "QM5") (pin "3") (pinfunction "D_3") (pintype "unspecified"))
    )
    (net (code "32") (name "Net-(DM5-C)") (class "Default")
      (node (ref "CM5") (pin "1") (pinfunction "1_1") (pintype "input"))
      (node (ref "DM5") (pin "1") (pinfunction "C_1") (pintype "unspecified"))
      (node (ref "J12VM5") (pin "1") (pinfunction "1_1") (pintype "bidirectional"))
      (node (ref "J5VM5") (pin "1") (pinfunction "1_1") (pintype "bidirectional"))
      (node (ref "J9VM5") (pin "1") (pinfunction "1_1") (pintype "bidirectional"))
      (node (ref "MOTOR5") (pin "1") (pinfunction "1_1") (pintype "unspecified"))
    )
    (net (code "33") (name "Net-(DM6-A)") (class "Default")
      (node (ref "CM6") (pin "2") (pinfunction "2_2") (pintype "input"))
      (node (ref "DM6") (pin "2") (pinfunction "A_2") (pintype "unspecified"))
      (node (ref "MOTOR6") (pin "2") (pinfunction "2_2") (pintype "unspecified"))
      (node (ref "QM6") (pin "3") (pinfunction "D_3") (pintype "unspecified"))
    )
    (net (code "34") (name "Net-(DM6-C)") (class "Default")
      (node (ref "CM6") (pin "1") (pinfunction "1_1") (pintype "input"))
      (node (ref "DM6") (pin "1") (pinfunction "C_1") (pintype "unspecified"))
      (node (ref "J12VM6") (pin "1") (pinfunction "1_1") (pintype "bidirectional"))
      (node (ref "J5VM6") (pin "1") (pinfunction "1_1") (pintype "bidirectional"))
      (node (ref "J9VM6") (pin "1") (pinfunction "1_1") (pintype "bidirectional"))
      (node (ref "MOTOR6") (pin "1") (pinfunction "1_1") (pintype "unspecified"))
    )
    (net (code "35") (name "Net-(DM7-A)") (class "Default")
      (node (ref "CM7") (pin "2") (pinfunction "2_2") (pintype "input"))
      (node (ref "DM7") (pin "2") (pinfunction "A_2") (pintype "unspecified"))
      (node (ref "MOTOR7") (pin "2") (pinfunction "2_2") (pintype "unspecified"))
      (node (ref "QM7") (pin "3") (pinfunction "D_3") (pintype "unspecified"))
    )
    (net (code "36") (name "Net-(DM7-C)") (class "Default")
      (node (ref "CM7") (pin "1") (pinfunction "1_1") (pintype "input"))
      (node (ref "DM7") (pin "1") (pinfunction "C_1") (pintype "unspecified"))
      (node (ref "J12VM7") (pin "1") (pinfunction "1_1") (pintype "bidirectional"))
      (node (ref "J5VM7") (pin "1") (pinfunction "1_1") (pintype "bidirectional"))
      (node (ref "J9VM7") (pin "1") (pinfunction "1_1") (pintype "bidirectional"))
      (node (ref "MOTOR7") (pin "1") (pinfunction "1_1") (pintype "unspecified"))
    )
    (net (code "37") (name "Net-(DM8-A)") (class "Default")
      (node (ref "CM8") (pin "2") (pinfunction "2_2") (pintype "input"))
      (node (ref "DM8") (pin "2") (pinfunction "A_2") (pintype "unspecified"))
      (node (ref "MOTOR8") (pin "2") (pinfunction "2_2") (pintype "unspecified"))
      (node (ref "QM8") (pin "3") (pinfunction "D_3") (pintype "unspecified"))
    )
    (net (code "38") (name "Net-(DM8-C)") (class "Default")
      (node (ref "CM8") (pin "1") (pinfunction "1_1") (pintype "input"))
      (node (ref "DM8") (pin "1") (pinfunction "C_1") (pintype "unspecified"))
      (node (ref "J12VM8") (pin "1") (pinfunction "1_1") (pintype "bidirectional"))
      (node (ref "J5VM8") (pin "1") (pinfunction "1_1") (pintype "bidirectional"))
      (node (ref "J9VM8") (pin "1") (pinfunction "1_1") (pintype "bidirectional"))
      (node (ref "MOTOR8") (pin "1") (pinfunction "1_1") (pintype "unspecified"))
    )
    (net (code "39") (name "Net-(DM9-A)") (class "Default")
      (node (ref "CM9") (pin "2") (pinfunction "2_2") (pintype "input"))
      (node (ref "DM9") (pin "2") (pinfunction "A_2") (pintype "unspecified"))
      (node (ref "MOTOR9") (pin "2") (pinfunction "2_2") (pintype "unspecified"))
      (node (ref "QM9") (pin "3") (pinfunction "D_3") (pintype "unspecified"))
    )
    (net (code "40") (name "Net-(DM9-C)") (class "Default")
      (node (ref "CM9") (pin "1") (pinfunction "1_1") (pintype "input"))
      (node (ref "DM9") (pin "1") (pinfunction "C_1") (pintype "unspecified"))
      (node (ref "J12VM9") (pin "1") (pinfunction "1_1") (pintype "bidirectional"))
      (node (ref "J5VM9") (pin "1") (pinfunction "1_1") (pintype "bidirectional"))
      (node (ref "J9VM9") (pin "1") (pinfunction "1_1") (pintype "bidirectional"))
      (node (ref "MOTOR9") (pin "1") (pinfunction "1_1") (pintype "unspecified"))
    )
    (net (code "41") (name "Net-(DM10-A)") (class "Default")
      (node (ref "CM10") (pin "2") (pinfunction "2_2") (pintype "input"))
      (node (ref "DM10") (pin "2") (pinfunction "A_2") (pintype "unspecified"))
      (node (ref "MOTOR10") (pin "2") (pinfunction "2_2") (pintype "unspecified"))
      (node (ref "QM10") (pin "3") (pinfunction "D_3") (pintype "unspecified"))
    )
    (net (code "42") (name "Net-(DM10-C)") (class "Default")
      (node (ref "CM10") (pin "1") (pinfunction "1_1") (pintype "input"))
      (node (ref "DM10") (pin "1") (pinfunction "C_1") (pintype "unspecified"))
      (node (ref "J12VM10") (pin "1") (pinfunction "1_1") (pintype "bidirectional"))
      (node (ref "J5VM10") (pin "1") (pinfunction "1_1") (pintype "bidirectional"))
      (node (ref "J9VM10") (pin "1") (pinfunction "1_1") (pintype "bidirectional"))
      (node (ref "MOTOR10") (pin "1") (pinfunction "1_1") (pintype "unspecified"))
    )
    (net (code "43") (name "Net-(DM11-A)") (class "Default")
      (node (ref "CM11") (pin "2") (pinfunction "2_2") (pintype "input"))
      (node (ref "DM11") (pin "2") (pinfunction "A_2") (pintype "unspecified"))
      (node (ref "MOTOR11") (pin "2") (pinfunction "2_2") (pintype "unspecified"))
      (node (ref "Q2") (pin "3") (pinfunction "D_3") (pintype "unspecified"))
    )
    (net (code "44") (name "Net-(DM11-C)") (class "Default")
      (node (ref "CM11") (pin "1") (pinfunction "1_1") (pintype "input"))
      (node (ref "DM11") (pin "1") (pinfunction "C_1") (pintype "unspecified"))
      (node (ref "J12VM11") (pin "1") (pinfunction "1_1") (pintype "bidirectional"))
      (node (ref "J5VM11") (pin "1") (pinfunction "1_1") (pintype "bidirectional"))
      (node (ref "J9VM11") (pin "1") (pinfunction "1_1") (pintype "bidirectional"))
      (node (ref "MOTOR11") (pin "1") (pinfunction "1_1") (pintype "unspecified"))
    )
    (net (code "45") (name "Net-(H4-Pad3)") (class "Default")
      (node (ref "H4") (pin "3") (pinfunction "3_3") (pintype "unspecified"))
      (node (ref "J2") (pin "28") (pinfunction "RESET_28") (pintype "unspecified"))
    )
    (net (code "46") (name "Net-(H5-Pad3)") (class "Default")
      (node (ref "H5") (pin "3") (pinfunction "3_3") (pintype "unspecified"))
      (node (ref "J2") (pin "3") (pinfunction "RESET_3") (pintype "unspecified"))
    )
    (net (code "47") (name "Net-(J2-AREF)") (class "Default")
      (node (ref "H4") (pin "13") (pinfunction "13_13") (pintype "unspecified"))
      (node (ref "J2") (pin "18") (pinfunction "AREF_18") (pintype "unspecified"))
    )
    (net (code "48") (name "Net-(L1-C)") (class "Default")
      (node (ref "L1") (pin "2") (pinfunction "C_2") (pintype "input"))
      (node (ref "RL8") (pin "2") (pinfunction "2_2") (pintype "input"))
    )
    (net (code "49") (name "Net-(L4-C)") (class "Default")
      (node (ref "L4") (pin "2") (pinfunction "C_2") (pintype "input"))
      (node (ref "RL4") (pin "2") (pinfunction "2_2") (pintype "input"))
    )
    (net (code "50") (name "Net-(L5-C)") (class "Default")
      (node (ref "L5") (pin "2") (pinfunction "C_2") (pintype "input"))
      (node (ref "RL5") (pin "2") (pinfunction "2_2") (pintype "input"))
    )
    (net (code "51") (name "Net-(L6-C)") (class "Default")
      (node (ref "L6") (pin "2") (pinfunction "C_2") (pintype "input"))
      (node (ref "RL6") (pin "2") (pinfunction "2_2") (pintype "input"))
    )
    (net (code "52") (name "Net-(L7-C)") (class "Default")
      (node (ref "L7") (pin "2") (pinfunction "C_2") (pintype "input"))
      (node (ref "RL7") (pin "2") (pinfunction "2_2") (pintype "input"))
    )
    (net (code "53") (name "Net-(L9-C)") (class "Default")
      (node (ref "L9") (pin "2") (pinfunction "C_2") (pintype "input"))
      (node (ref "RL9") (pin "2") (pinfunction "2_2") (pintype "input"))
    )
    (net (code "54") (name "Net-(L10-C)") (class "Default")
      (node (ref "L10") (pin "2") (pinfunction "C_2") (pintype "input"))
      (node (ref "RL10") (pin "2") (pinfunction "2_2") (pintype "input"))
    )
    (net (code "55") (name "Net-(L11-C)") (class "Default")
      (node (ref "L11") (pin "2") (pinfunction "C_2") (pintype "input"))
      (node (ref "RL11") (pin "2") (pinfunction "2_2") (pintype "input"))
    )
    (net (code "56") (name "Net-(L12V-C)") (class "Default")
      (node (ref "L12V") (pin "2") (pinfunction "C_2") (pintype "input"))
      (node (ref "R15") (pin "1") (pinfunction "1_1") (pintype "input"))
    )
    (net (code "58") (name "unconnected-(P2-Pad4)") (class "Default")
      (node (ref "P2") (pin "4") (pinfunction "4_4") (pintype "input"))
    )
    (net (code "59") (name "unconnected-(P2-Pad5)") (class "Default")
      (node (ref "P2") (pin "5") (pinfunction "5_5") (pintype "input"))
    )
    (net (code "60") (name "unconnected-(P3-Pad4)") (class "Default")
      (node (ref "P3") (pin "4") (pinfunction "4_4") (pintype "input"))
    )
    (net (code "61") (name "unconnected-(P3-Pad5)") (class "Default")
      (node (ref "P3") (pin "5") (pinfunction "5_5") (pintype "input"))
    )
  )
)
